# OMD_30G_IMU.net
KiCad netlist of a schematic drawn in Altium Designer
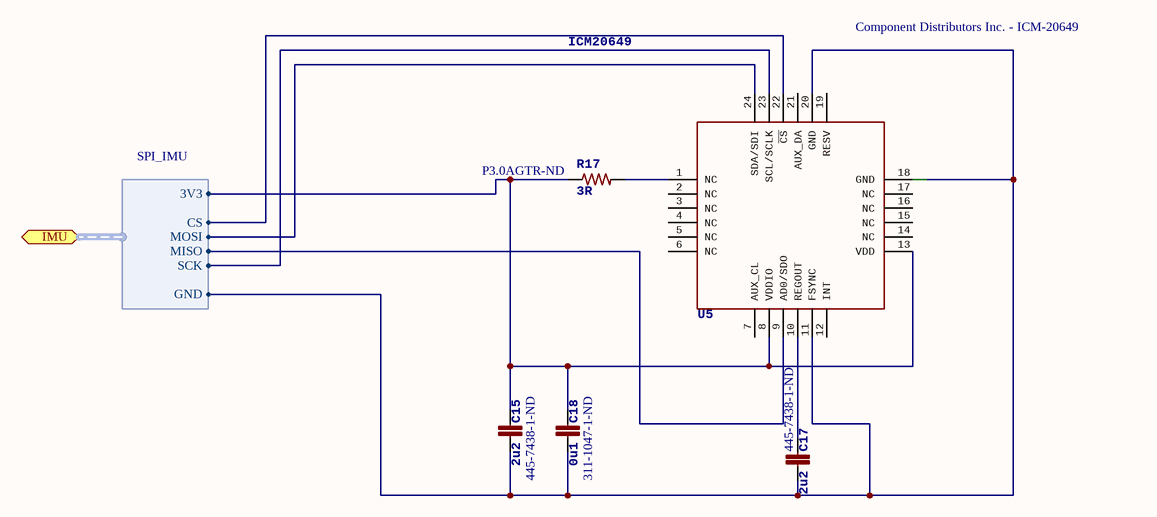
[diagram p0: OMD_30G_IMU.SchDoc]

(export (version "E")
  (design (tool "Eeschema 10.0.6"))
  (components
    (comp (ref "C15")
      (value "2u2")
      (footprint "0603-CAP")
      (description "CAP CER 2.2UF 16V 10% X6S 0603")
      (fields (field (name "SUPPLIER PART NUMBER 1") "445-7438-1-ND"))
      (libsource (lib "OMD") (part "CAP0603"))
    )
    (comp (ref "C17")
      (value "2u2")
      (footprint "0603-CAP")
      (description "CAP CER 2.2UF 16V 10% X6S 0603")
      (fields (field (name "SUPPLIER PART NUMBER 1") "445-7438-1-ND"))
      (libsource (lib "OMD") (part "CAP0603"))
    )
    (comp (ref "C18")
      (value "0u1")
      (footprint "0402-CAP")
      (description "CAP CER 0.1UF 16V Y5V 0402")
      (fields (field (name "SUPPLIER PART NUMBER 1") "311-1047-1-ND"))
      (libsource (lib "OMD") (part "CAP0402"))
    )
    (comp (ref "R17")
      (value "3R")
      (footprint "0201-RES")
      (description "RES 3OHM 1/16W 1% 0201 SMD")
      (fields (field (name "SUPPLIER PART NUMBER 1") "P3.0AGTR-ND"))
      (libsource (lib "OMD") (part "RESISTOR0402-RES"))
    )
    (comp (ref "U5")
      (value "ICM20649")
      (footprint "ICM20649")
      (fields (field (name "SUPPLIER PART NUMBER 1") "Component Distributors Inc. - ICM-20649"))
      (libsource (lib "OMD") (part "ICM20649"))
    )
  )
  (nets
    (net (code "2") (name "/3V3") (class "Default")
      (node (ref "C15") (pin "1") (pinfunction "1_1") (pintype "passive"))
      (node (ref "C18") (pin "P$1") (pinfunction "1_P$1") (pintype "passive"))
      (node (ref "R17") (pin "1") (pinfunction "1_1") (pintype "passive"))
      (node (ref "U5") (pin "13") (pinfunction "VDD_13") (pintype "passive"))
      (node (ref "U5") (pin "8") (pinfunction "VDDIO_8") (pintype "passive"))
    )
    (net (code "3") (name "/CS") (class "Default")
      (node (ref "U5") (pin "22") (pinfunction "~{CS}_22") (pintype "passive"))
    )
    (net (code "4") (name "/GND") (class "Default")
      (node (ref "C15") (pin "2") (pinfunction "2_2") (pintype "passive"))
      (node (ref "C17") (pin "2") (pinfunction "2_2") (pintype "passive"))
      (node (ref "C18") (pin "P$2") (pinfunction "2_P$2") (pintype "passive"))
      (node (ref "U5") (pin "11") (pinfunction "FSYNC_11") (pintype "passive"))
      (node (ref "U5") (pin "18") (pinfunction "GND_18") (pintype "passive"))
      (node (ref "U5") (pin "20") (pinfunction "GND_20") (pintype "passive"))
    )
    (net (code "5") (name "/MISO") (class "Default")
      (node (ref "U5") (pin "9") (pinfunction "AD0/SDO_9") (pintype "passive"))
    )
    (net (code "6") (name "/MOSI") (class "Default")
      (node (ref "U5") (pin "24") (pinfunction "SDA/SDI_24") (pintype "passive"))
    )
    (net (code "7") (name "/SCK") (class "Default")
      (node (ref "U5") (pin "23") (pinfunction "SCL/SCLK_23") (pintype "passive"))
    )
    (net (code "9") (name "Net-(R17-Pad2)") (class "Default")
      (node (ref "R17") (pin "2") (pinfunction "2_2") (pintype "passive"))
      (node (ref "U5") (pin "1") (pinfunction "NC_1") (pintype "passive"))
    )
    (net (code "10") (name "Net-(U5-REGOUT)") (class "Default")
      (node (ref "C17") (pin "1") (pinfunction "1_1") (pintype "passive"))
      (node (ref "U5") (pin "10") (pinfunction "REGOUT_10") (pintype "passive"))
    )
    (net (code "11") (name "unconnected-(U5-AUX_CL-Pad7)") (class "Default")
      (node (ref "U5") (pin "7") (pinfunction "AUX_CL_7") (pintype "passive"))
    )
    (net (code "12") (name "unconnected-(U5-AUX_DA-Pad21)") (class "Default")
      (node (ref "U5") (pin "21") (pinfunction "AUX_DA_21") (pintype "passive"))
    )
    (net (code "13") (name "unconnected-(U5-INT-Pad12)") (class "Default")
      (node (ref "U5") (pin "12") (pinfunction "INT_12") (pintype "passive"))
    )
    (net (code "14") (name "unconnected-(U5-NC-Pad2)") (class "Default")
      (node (ref "U5") (pin "2") (pinfunction "NC_2") (pintype "passive"))
    )
    (net (code "15") (name "unconnected-(U5-NC-Pad3)") (class "Default")
      (node (ref "U5") (pin "3") (pinfunction "NC_3") (pintype "passive"))
    )
    (net (code "16") (name "unconnected-(U5-NC-Pad4)") (class "Default")
      (node (ref "U5") (pin "4") (pinfunction "NC_4") (pintype "passive"))
    )
    (net (code "17") (name "unconnected-(U5-NC-Pad5)") (class "Default")
      (node (ref "U5") (pin "5") (pinfunction "NC_5") (pintype "passive"))
    )
    (net (code "18") (name "unconnected-(U5-NC-Pad6)") (class "Default")
      (node (ref "U5") (pin "6") (pinfunction "NC_6") (pintype "passive"))
    )
    (net (code "19") (name "unconnected-(U5-NC-Pad14)") (class "Default")
      (node (ref "U5") (pin "14") (pinfunction "NC_14") (pintype "passive"))
    )
    (net (code "20") (name "unconnected-(U5-NC-Pad15)") (class "Default")
      (node (ref "U5") (pin "15") (pinfunction "NC_15") (pintype "passive"))
    )
    (net (code "21") (name "unconnected-(U5-NC-Pad16)") (class "Default")
      (node (ref "U5") (pin "16") (pinfunction "NC_16") (pintype "passive"))
    )
    (net (code "22") (name "unconnected-(U5-NC-Pad17)") (class "Default")
      (node (ref "U5") (pin "17") (pinfunction "NC_17") (pintype "passive"))
    )
    (net (code "23") (name "unconnected-(U5-RESV-Pad19)") (class "Default")
      (node (ref "U5") (pin "19") (pinfunction "RESV_19") (pintype "passive"))
    )
  )
)
